# tiny44.net
KiCad netlist of a schematic drawn in EAGLE
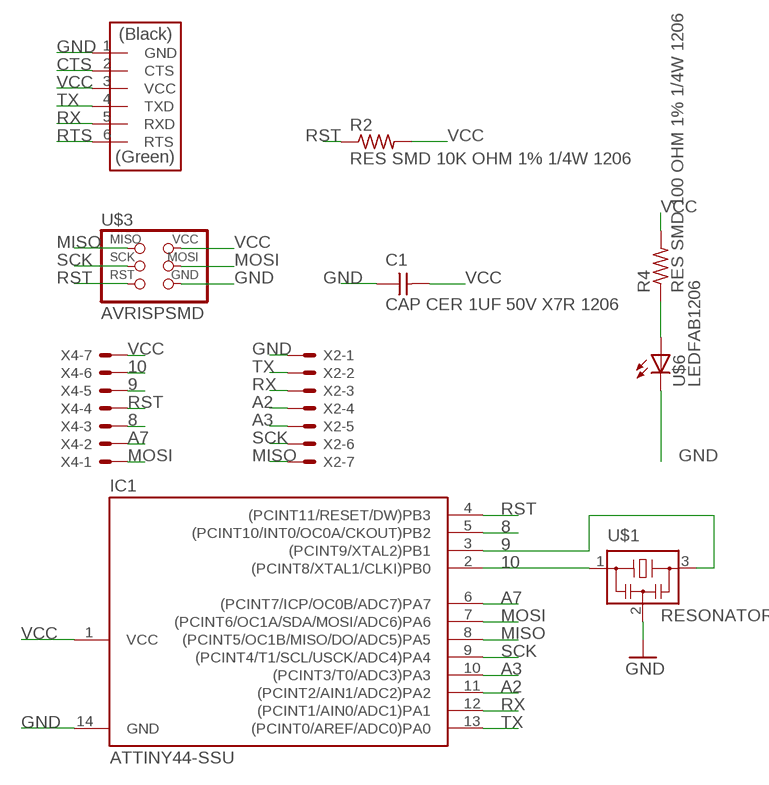
[diagram p0: schematic, sheet 1]

(export (version "E")
  (design (tool "Eeschema 10.0.6"))
  (components
    (comp (ref "C1")
      (value "CAP CER 1UF 50V X7R 1206")
      (footprint "eagle-import:C1206FAB")
      (libsource (lib "eagle-import") (part "CAP-UNPOLARIZEDFAB"))
    )
    (comp (ref "IC1")
      (value "ATTINY44-SSU")
      (footprint "eagle-import:SOIC14")
      (libsource (lib "eagle-import") (part "ATTINY44-SSU"))
    )
    (comp (ref "R2")
      (value "RES SMD 10K OHM 1% 1/4W 1206")
      (footprint "eagle-import:R1206FAB")
      (libsource (lib "eagle-import") (part "RES-US1206FAB"))
    )
    (comp (ref "R4")
      (value "RES SMD 100 OHM 1% 1/4W 1206")
      (footprint "eagle-import:R1206FAB")
      (libsource (lib "eagle-import") (part "RES-US1206FAB"))
    )
    (comp (ref "U$1")
      (value "RESONATOR")
      (footprint "eagle-import:EFOBM")
      (fields (field (name "MF") "Abracon Corporation") (field (name "MPN") "AWSCR-20.00MTD-T"))
      (libsource (lib "eagle-import") (part "RESONATOR"))
    )
    (comp (ref "U$2")
      (value "FTDI-SMD-HEADER")
      (footprint "eagle-import:1X06SMD")
      (libsource (lib "eagle-import") (part "FTDI-SMD-HEADER"))
    )
    (comp (ref "U$3")
      (value "AVRISPSMD")
      (footprint "eagle-import:2X03SMD")
      (libsource (lib "eagle-import") (part "AVRISPSMD"))
    )
    (comp (ref "U$6")
      (value "LEDFAB1206")
      (footprint "eagle-import:LED1206FAB")
      (libsource (lib "eagle-import") (part "LEDFAB1206"))
    )
    (comp (ref "X2")
      (value "KK-156-7")
      (footprint "eagle-import:KK-156-7")
      (fields (field (name "MF") "MOLEX"))
      (libsource (lib "eagle-import") (part "KK-156-7"))
    )
    (comp (ref "X4")
      (value "KK-156-7")
      (footprint "eagle-import:KK-156-7")
      (fields (field (name "MF") "MOLEX"))
      (libsource (lib "eagle-import") (part "KK-156-7"))
    )
  )
  (nets
    (net (code "1") (name "/8") (class "Default")
      (node (ref "IC1") (pin "5") (pinfunction "(PCINT10/INT0/OC0A/CKOUT)PB2_5") (pintype "bidirectional"))
      (node (ref "X4") (pin "3") (pinfunction "S_3") (pintype "passive"))
    )
    (net (code "2") (name "/9") (class "Default")
      (node (ref "IC1") (pin "3") (pinfunction "(PCINT9/XTAL2)PB1_3") (pintype "bidirectional"))
      (node (ref "U$1") (pin "3") (pinfunction "3_3") (pintype "passive"))
      (node (ref "X4") (pin "5") (pinfunction "S_5") (pintype "passive"))
    )
    (net (code "3") (name "/10") (class "Default")
      (node (ref "IC1") (pin "2") (pinfunction "(PCINT8/XTAL1/CLKI)PB0_2") (pintype "bidirectional"))
      (node (ref "U$1") (pin "1") (pinfunction "1_1") (pintype "passive"))
      (node (ref "X4") (pin "6") (pinfunction "S_6") (pintype "passive"))
    )
    (net (code "4") (name "/A2") (class "Default")
      (node (ref "IC1") (pin "11") (pinfunction "(PCINT2/AIN1/ADC2)PA2_11") (pintype "bidirectional"))
      (node (ref "X2") (pin "4") (pinfunction "S_4") (pintype "passive"))
    )
    (net (code "5") (name "/A3") (class "Default")
      (node (ref "IC1") (pin "10") (pinfunction "(PCINT3/T0/ADC3)PA3_10") (pintype "bidirectional"))
      (node (ref "X2") (pin "5") (pinfunction "S_5") (pintype "passive"))
    )
    (net (code "6") (name "/A7") (class "Default")
      (node (ref "IC1") (pin "6") (pinfunction "(PCINT7/ICP/OC0B/ADC7)PA7_6") (pintype "bidirectional"))
      (node (ref "X4") (pin "2") (pinfunction "S_2") (pintype "passive"))
    )
    (net (code "7") (name "/CTS") (class "Default")
      (node (ref "U$2") (pin "2") (pinfunction "CTS_2") (pintype "bidirectional"))
    )
    (net (code "8") (name "/MISO") (class "Default")
      (node (ref "IC1") (pin "8") (pinfunction "(PCINT5/OC1B/MISO/DO/ADC5)PA5_8") (pintype "bidirectional"))
      (node (ref "U$3") (pin "1") (pinfunction "MISO_1") (pintype "passive"))
      (node (ref "X2") (pin "7") (pinfunction "S_7") (pintype "passive"))
    )
    (net (code "9") (name "/MOSI") (class "Default")
      (node (ref "IC1") (pin "7") (pinfunction "(PCINT6/OC1A/SDA/MOSI/ADC6)PA6_7") (pintype "bidirectional"))
      (node (ref "U$3") (pin "4") (pinfunction "MOSI_4") (pintype "passive"))
      (node (ref "X4") (pin "1") (pinfunction "S_1") (pintype "passive"))
    )
    (net (code "10") (name "/RST") (class "Default")
      (node (ref "IC1") (pin "4") (pinfunction "(PCINT11/RESET/DW)PB3_4") (pintype "bidirectional"))
      (node (ref "R2") (pin "1") (pinfunction "1_1") (pintype "passive"))
      (node (ref "U$3") (pin "5") (pinfunction "RST_5") (pintype "passive"))
      (node (ref "X4") (pin "4") (pinfunction "S_4") (pintype "passive"))
    )
    (net (code "11") (name "/RTS") (class "Default")
      (node (ref "U$2") (pin "6") (pinfunction "RTS_6") (pintype "bidirectional"))
    )
    (net (code "12") (name "/RX") (class "Default")
      (node (ref "IC1") (pin "12") (pinfunction "(PCINT1/AIN0/ADC1)PA1_12") (pintype "bidirectional"))
      (node (ref "U$2") (pin "5") (pinfunction "RXD_5") (pintype "bidirectional"))
      (node (ref "X2") (pin "3") (pinfunction "S_3") (pintype "passive"))
    )
    (net (code "13") (name "/SCK") (class "Default")
      (node (ref "IC1") (pin "9") (pinfunction "(PCINT4/T1/SCL/USCK/ADC4)PA4_9") (pintype "bidirectional"))
      (node (ref "U$3") (pin "3") (pinfunction "SCK_3") (pintype "passive"))
      (node (ref "X2") (pin "6") (pinfunction "S_6") (pintype "passive"))
    )
    (net (code "14") (name "/TX") (class "Default")
      (node (ref "IC1") (pin "13") (pinfunction "(PCINT0/AREF/ADC0)PA0_13") (pintype "bidirectional"))
      (node (ref "U$2") (pin "4") (pinfunction "TXD_4") (pintype "bidirectional"))
      (node (ref "X2") (pin "2") (pinfunction "S_2") (pintype "passive"))
    )
    (net (code "15") (name "/VCC") (class "Default")
      (node (ref "C1") (pin "2") (pinfunction "2_2") (pintype "passive"))
      (node (ref "IC1") (pin "1") (pinfunction "VCC_1") (pintype "power_in"))
      (node (ref "R2") (pin "2") (pinfunction "2_2") (pintype "passive"))
      (node (ref "R4") (pin "2") (pinfunction "2_2") (pintype "passive"))
      (node (ref "U$2") (pin "3") (pinfunction "VCC_3") (pintype "bidirectional"))
      (node (ref "U$3") (pin "2") (pinfunction "VCC_2") (pintype "passive"))
      (node (ref "X4") (pin "7") (pinfunction "S_7") (pintype "passive"))
    )
    (net (code "16") (name "GND") (class "Default")
      (node (ref "C1") (pin "1") (pinfunction "1_1") (pintype "passive"))
      (node (ref "IC1") (pin "14") (pinfunction "GND_14") (pintype "power_in"))
      (node (ref "U$1") (pin "2") (pinfunction "2_2") (pintype "passive"))
      (node (ref "U$2") (pin "1") (pinfunction "GND_1") (pintype "bidirectional"))
      (node (ref "U$3") (pin "6") (pinfunction "GND_6") (pintype "passive"))
      (node (ref "U$6") (pin "2") (pinfunction "C_2") (pintype "passive"))
      (node (ref "X2") (pin "1") (pinfunction "S_1") (pintype "passive"))
    )
    (net (code "17") (name "Net-(U$6-A)") (class "Default")
      (node (ref "R4") (pin "1") (pinfunction "1_1") (pintype "passive"))
      (node (ref "U$6") (pin "1") (pinfunction "A_1") (pintype "passive"))
    )
  )
)
